# paizhen.net
KiCad netlist of a schematic drawn in Altium Designer
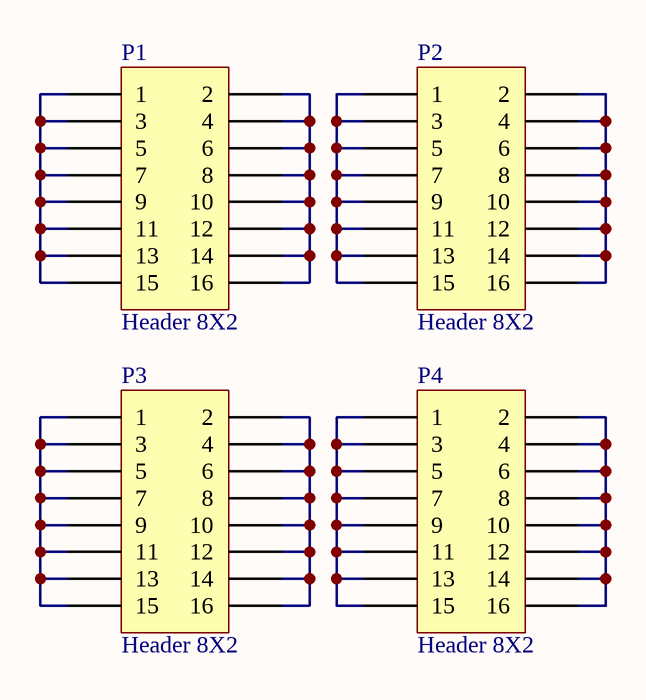
[diagram p0: paizhen.SchDoc]

(export (version "E")
  (design (tool "Eeschema 10.0.6"))
  (components
    (comp (ref "P1")
      (value "Header 8X2")
      (footprint "HDR2X8")
      (description "Header, 8-Pin, Dual row")
      (fields (field (name "PUBLISHER") "Altium Limited"))
      (libsource (lib "Miscellaneous Connectors") (part "Header 8X2"))
    )
    (comp (ref "P2")
      (value "Header 8X2")
      (footprint "HDR2X8")
      (description "Header, 8-Pin, Dual row")
      (fields (field (name "PUBLISHER") "Altium Limited"))
      (libsource (lib "Miscellaneous Connectors") (part "Header 8X2"))
    )
    (comp (ref "P3")
      (value "Header 8X2")
      (footprint "HDR2X8")
      (description "Header, 8-Pin, Dual row")
      (fields (field (name "PUBLISHER") "Altium Limited"))
      (libsource (lib "Miscellaneous Connectors") (part "Header 8X2"))
    )
    (comp (ref "P4")
      (value "Header 8X2")
      (footprint "HDR2X8")
      (description "Header, 8-Pin, Dual row")
      (fields (field (name "PUBLISHER") "Altium Limited"))
      (libsource (lib "Miscellaneous Connectors") (part "Header 8X2"))
    )
  )
  (nets
    (net (code "1") (name "Net-(P1-Pad1)") (class "Default")
      (node (ref "P1") (pin "1") (pinfunction "1_1") (pintype "passive"))
      (node (ref "P1") (pin "11") (pinfunction "11_11") (pintype "passive"))
      (node (ref "P1") (pin "13") (pinfunction "13_13") (pintype "passive"))
      (node (ref "P1") (pin "15") (pinfunction "15_15") (pintype "passive"))
      (node (ref "P1") (pin "3") (pinfunction "3_3") (pintype "passive"))
      (node (ref "P1") (pin "5") (pinfunction "5_5") (pintype "passive"))
      (node (ref "P1") (pin "7") (pinfunction "7_7") (pintype "passive"))
      (node (ref "P1") (pin "9") (pinfunction "9_9") (pintype "passive"))
    )
    (net (code "2") (name "Net-(P1-Pad10)") (class "Default")
      (node (ref "P1") (pin "10") (pinfunction "10_10") (pintype "passive"))
      (node (ref "P1") (pin "12") (pinfunction "12_12") (pintype "passive"))
      (node (ref "P1") (pin "14") (pinfunction "14_14") (pintype "passive"))
      (node (ref "P1") (pin "16") (pinfunction "16_16") (pintype "passive"))
      (node (ref "P1") (pin "2") (pinfunction "2_2") (pintype "passive"))
      (node (ref "P1") (pin "4") (pinfunction "4_4") (pintype "passive"))
      (node (ref "P1") (pin "6") (pinfunction "6_6") (pintype "passive"))
      (node (ref "P1") (pin "8") (pinfunction "8_8") (pintype "passive"))
    )
    (net (code "3") (name "Net-(P2-Pad1)") (class "Default")
      (node (ref "P2") (pin "1") (pinfunction "1_1") (pintype "passive"))
      (node (ref "P2") (pin "11") (pinfunction "11_11") (pintype "passive"))
      (node (ref "P2") (pin "13") (pinfunction "13_13") (pintype "passive"))
      (node (ref "P2") (pin "15") (pinfunction "15_15") (pintype "passive"))
      (node (ref "P2") (pin "3") (pinfunction "3_3") (pintype "passive"))
      (node (ref "P2") (pin "5") (pinfunction "5_5") (pintype "passive"))
      (node (ref "P2") (pin "7") (pinfunction "7_7") (pintype "passive"))
      (node (ref "P2") (pin "9") (pinfunction "9_9") (pintype "passive"))
    )
    (net (code "4") (name "Net-(P2-Pad10)") (class "Default")
      (node (ref "P2") (pin "10") (pinfunction "10_10") (pintype "passive"))
      (node (ref "P2") (pin "12") (pinfunction "12_12") (pintype "passive"))
      (node (ref "P2") (pin "14") (pinfunction "14_14") (pintype "passive"))
      (node (ref "P2") (pin "16") (pinfunction "16_16") (pintype "passive"))
      (node (ref "P2") (pin "2") (pinfunction "2_2") (pintype "passive"))
      (node (ref "P2") (pin "4") (pinfunction "4_4") (pintype "passive"))
      (node (ref "P2") (pin "6") (pinfunction "6_6") (pintype "passive"))
      (node (ref "P2") (pin "8") (pinfunction "8_8") (pintype "passive"))
    )
    (net (code "5") (name "Net-(P3-Pad1)") (class "Default")
      (node (ref "P3") (pin "1") (pinfunction "1_1") (pintype "passive"))
      (node (ref "P3") (pin "11") (pinfunction "11_11") (pintype "passive"))
      (node (ref "P3") (pin "13") (pinfunction "13_13") (pintype "passive"))
      (node (ref "P3") (pin "15") (pinfunction "15_15") (pintype "passive"))
      (node (ref "P3") (pin "3") (pinfunction "3_3") (pintype "passive"))
      (node (ref "P3") (pin "5") (pinfunction "5_5") (pintype "passive"))
      (node (ref "P3") (pin "7") (pinfunction "7_7") (pintype "passive"))
      (node (ref "P3") (pin "9") (pinfunction "9_9") (pintype "passive"))
    )
    (net (code "6") (name "Net-(P3-Pad10)") (class "Default")
      (node (ref "P3") (pin "10") (pinfunction "10_10") (pintype "passive"))
      (node (ref "P3") (pin "12") (pinfunction "12_12") (pintype "passive"))
      (node (ref "P3") (pin "14") (pinfunction "14_14") (pintype "passive"))
      (node (ref "P3") (pin "16") (pinfunction "16_16") (pintype "passive"))
      (node (ref "P3") (pin "2") (pinfunction "2_2") (pintype "passive"))
      (node (ref "P3") (pin "4") (pinfunction "4_4") (pintype "passive"))
      (node (ref "P3") (pin "6") (pinfunction "6_6") (pintype "passive"))
      (node (ref "P3") (pin "8") (pinfunction "8_8") (pintype "passive"))
    )
    (net (code "7") (name "Net-(P4-Pad1)") (class "Default")
      (node (ref "P4") (pin "1") (pinfunction "1_1") (pintype "passive"))
      (node (ref "P4") (pin "11") (pinfunction "11_11") (pintype "passive"))
      (node (ref "P4") (pin "13") (pinfunction "13_13") (pintype "passive"))
      (node (ref "P4") (pin "15") (pinfunction "15_15") (pintype "passive"))
      (node (ref "P4") (pin "3") (pinfunction "3_3") (pintype "passive"))
      (node (ref "P4") (pin "5") (pinfunction "5_5") (pintype "passive"))
      (node (ref "P4") (pin "7") (pinfunction "7_7") (pintype "passive"))
      (node (ref "P4") (pin "9") (pinfunction "9_9") (pintype "passive"))
    )
    (net (code "8") (name "Net-(P4-Pad10)") (class "Default")
      (node (ref "P4") (pin "10") (pinfunction "10_10") (pintype "passive"))
      (node (ref "P4") (pin "12") (pinfunction "12_12") (pintype "passive"))
      (node (ref "P4") (pin "14") (pinfunction "14_14") (pintype "passive"))
      (node (ref "P4") (pin "16") (pinfunction "16_16") (pintype "passive"))
      (node (ref "P4") (pin "2") (pinfunction "2_2") (pintype "passive"))
      (node (ref "P4") (pin "4") (pinfunction "4_4") (pintype "passive"))
      (node (ref "P4") (pin "6") (pinfunction "6_6") (pintype "passive"))
      (node (ref "P4") (pin "8") (pinfunction "8_8") (pintype "passive"))
    )
  )
)
